# DC_DC_15V_AND_VAR.net
KiCad netlist of a schematic drawn in Altium Designer
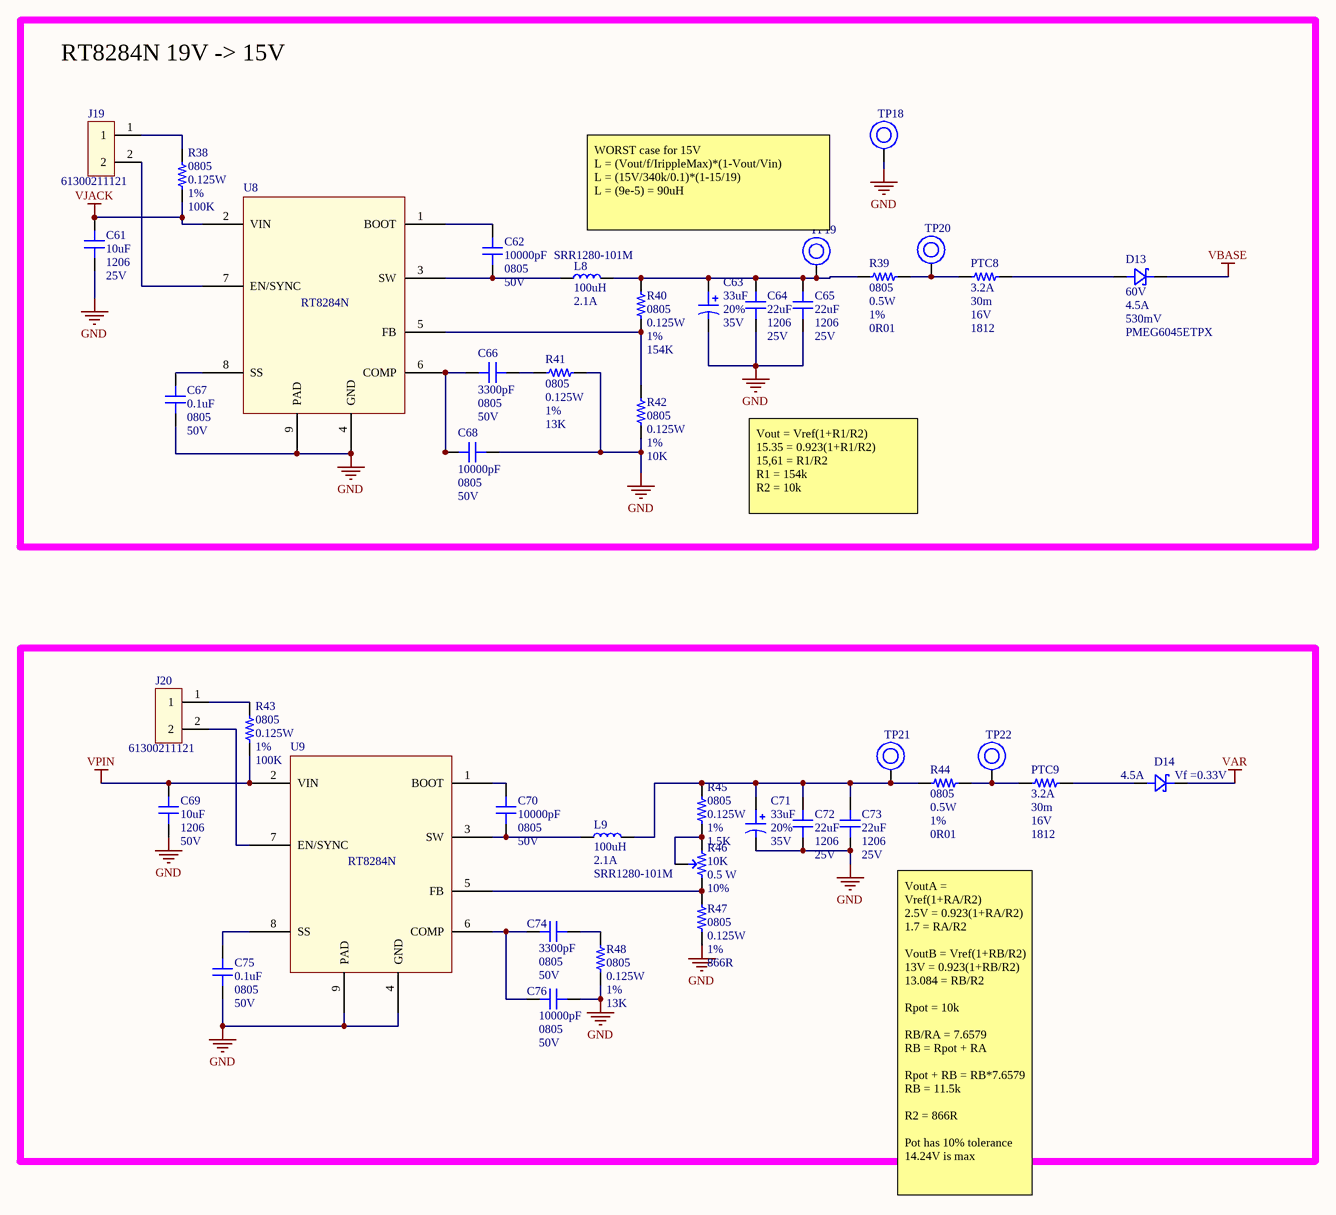
[diagram p0: DC_DC_15V_AND_VAR.SchDoc]

(export (version "E")
  (design (tool "Eeschema 10.0.6"))
  (components
    (comp (ref "C61")
      (value "10uF")
      (footprint "CAP_1206")
      (description "CAP CER 10uF 25V 1206")
      (fields
        (field (name "PART NUMBER") "CL31A106KAHNFNE‎")
        (field (name "PACKAGE") "1206")
        (field (name "VOLTAGE") "25V")
        (field (name "Comment") "CAP_‎CL31A106KAHNFNE‎")
      )
      (libsource (lib "SecureBot") (part "CAP_‎CL31A106KAHNFNE‎"))
    )
    (comp (ref "C62")
      (value "10000pF")
      (footprint "CAP_0805")
      (description "CAP CER 10000pF 50V 0805")
      (fields
        (field (name "PART NUMBER") "‎CL21B103KBANNNC")
        (field (name "PACKAGE") "0805")
        (field (name "VOLTAGE") "50V")
        (field (name "Comment") "CAP_‎‎‎‎CL21B103KBANNNC")
      )
      (libsource (lib "SecureBot") (part "CAP_‎‎‎‎CL21B103KBANNNC"))
    )
    (comp (ref "C63")
      (value "33uF")
      (footprint "CAP ALU - 6.3mm DIA")
      (description "CAP ALU 33µF 35V")
      (fields
        (field (name "PART NUMBER") "EEE-FK1V330P")
        (field (name "TOLERANCE") "20%")
        (field (name "VOLTAGE") "35V")
        (field (name "Comment") "CAP_EEE-FK1V330P")
      )
      (libsource (lib "SecureBot") (part "CAP_EEE-FK1V330P"))
    )
    (comp (ref "C64")
      (value "22uF")
      (footprint "CAP_1206")
      (description "CAP CER 22uF 25V 1206")
      (fields
        (field (name "PART NUMBER") "CL31A226KAHNNNE‎")
        (field (name "PACKAGE") "1206")
        (field (name "VOLTAGE") "25V")
        (field (name "Comment") "CAP_‎‎CL31A226KAHNNNE‎")
      )
      (libsource (lib "SecureBot") (part "CAP_‎‎CL31A226KAHNNNE‎"))
    )
    (comp (ref "C65")
      (value "22uF")
      (footprint "CAP_1206")
      (description "CAP CER 22uF 25V 1206")
      (fields
        (field (name "PART NUMBER") "CL31A226KAHNNNE‎")
        (field (name "PACKAGE") "1206")
        (field (name "VOLTAGE") "25V")
        (field (name "Comment") "CAP_‎‎CL31A226KAHNNNE‎")
      )
      (libsource (lib "SecureBot") (part "CAP_‎‎CL31A226KAHNNNE‎"))
    )
    (comp (ref "C66")
      (value "3300pF")
      (footprint "CAP_0805")
      (description "CAP CER 3300pF 50V 0805")
      (fields
        (field (name "PART NUMBER") "CL21B332KBANNNC‎")
        (field (name "PACKAGE") "0805")
        (field (name "VOLTAGE") "50V")
        (field (name "Comment") "CAP_CL21B332KBANNNC‎")
      )
      (libsource (lib "SecureBot") (part "CAP_CL21B332KBANNNC‎"))
    )
    (comp (ref "C67")
      (value "0.1uF")
      (footprint "CAP_0805")
      (description "CAP CER 0.1uF 50V 0805")
      (fields
        (field (name "PART NUMBER") "CC0805KRX7R9BB104‎")
        (field (name "PACKAGE") "0805")
        (field (name "VOLTAGE") "50V")
        (field (name "Comment") "CAP_CC0805KRX7R9BB104‎")
      )
      (libsource (lib "SecureBot") (part "CAP_CC0805KRX7R9BB104‎"))
    )
    (comp (ref "C68")
      (value "10000pF")
      (footprint "CAP_0805")
      (description "CAP CER 10000pF 50V 0805")
      (fields
        (field (name "PART NUMBER") "‎CL21B103KBANNNC")
        (field (name "PACKAGE") "0805")
        (field (name "VOLTAGE") "50V")
        (field (name "Comment") "CAP_‎‎‎‎CL21B103KBANNNC")
      )
      (libsource (lib "SecureBot") (part "CAP_‎‎‎‎CL21B103KBANNNC"))
    )
    (comp (ref "C69")
      (value "10uF")
      (footprint "CAP_1206")
      (description "CAP CER 10uF 50V 1206")
      (fields
        (field (name "PART NUMBER") "GRT31CR61H106ME01L‎")
        (field (name "PACKAGE") "1206")
        (field (name "VOLTAGE") "50V")
        (field (name "Comment") "CAP_GRT31CR61H106ME01L‎")
      )
      (libsource (lib "SecureBot") (part "CAP_GRT31CR61H106ME01L‎"))
    )
    (comp (ref "C70")
      (value "10000pF")
      (footprint "CAP_0805")
      (description "CAP CER 10000pF 50V 0805")
      (fields
        (field (name "PART NUMBER") "‎CL21B103KBANNNC")
        (field (name "PACKAGE") "0805")
        (field (name "VOLTAGE") "50V")
        (field (name "Comment") "CAP_‎‎‎‎CL21B103KBANNNC")
      )
      (libsource (lib "SecureBot") (part "CAP_‎‎‎‎CL21B103KBANNNC"))
    )
    (comp (ref "C71")
      (value "33uF")
      (footprint "CAP ALU - 6.3mm DIA")
      (description "CAP ALU 33µF 35V")
      (fields
        (field (name "PART NUMBER") "EEE-FK1V330P")
        (field (name "TOLERANCE") "20%")
        (field (name "VOLTAGE") "35V")
        (field (name "Comment") "CAP_EEE-FK1V330P")
      )
      (libsource (lib "SecureBot") (part "CAP_EEE-FK1V330P"))
    )
    (comp (ref "C72")
      (value "22uF")
      (footprint "CAP_1206")
      (description "CAP CER 22uF 25V 1206")
      (fields
        (field (name "PART NUMBER") "CL31A226KAHNNNE‎")
        (field (name "PACKAGE") "1206")
        (field (name "VOLTAGE") "25V")
        (field (name "Comment") "CAP_‎‎CL31A226KAHNNNE‎")
      )
      (libsource (lib "SecureBot") (part "CAP_‎‎CL31A226KAHNNNE‎"))
    )
    (comp (ref "C73")
      (value "22uF")
      (footprint "CAP_1206")
      (description "CAP CER 22uF 25V 1206")
      (fields
        (field (name "PART NUMBER") "CL31A226KAHNNNE‎")
        (field (name "PACKAGE") "1206")
        (field (name "VOLTAGE") "25V")
        (field (name "Comment") "CAP_‎‎CL31A226KAHNNNE‎")
      )
      (libsource (lib "SecureBot") (part "CAP_‎‎CL31A226KAHNNNE‎"))
    )
    (comp (ref "C74")
      (value "3300pF")
      (footprint "CAP_0805")
      (description "CAP CER 3300pF 50V 0805")
      (fields
        (field (name "PART NUMBER") "CL21B332KBANNNC‎")
        (field (name "PACKAGE") "0805")
        (field (name "VOLTAGE") "50V")
        (field (name "Comment") "CAP_CL21B332KBANNNC‎")
      )
      (libsource (lib "SecureBot") (part "CAP_CL21B332KBANNNC‎"))
    )
    (comp (ref "C75")
      (value "0.1uF")
      (footprint "CAP_0805")
      (description "CAP CER 0.1uF 50V 0805")
      (fields
        (field (name "PART NUMBER") "CC0805KRX7R9BB104‎")
        (field (name "PACKAGE") "0805")
        (field (name "VOLTAGE") "50V")
        (field (name "Comment") "CAP_CC0805KRX7R9BB104‎")
      )
      (libsource (lib "SecureBot") (part "CAP_CC0805KRX7R9BB104‎"))
    )
    (comp (ref "C76")
      (value "10000pF")
      (footprint "CAP_0805")
      (description "CAP CER 10000pF 50V 0805")
      (fields
        (field (name "PART NUMBER") "‎CL21B103KBANNNC")
        (field (name "PACKAGE") "0805")
        (field (name "VOLTAGE") "50V")
        (field (name "Comment") "CAP_‎‎‎‎CL21B103KBANNNC")
      )
      (libsource (lib "SecureBot") (part "CAP_‎‎‎‎CL21B103KBANNNC"))
    )
    (comp (ref "D13")
      (value "DIODE_SCH_PMEG6045ETPX")
      (footprint "DO-214AC_SOD128")
      (description "Diode Schottky 60V 4.5A Surface Mount CFP5")
      (fields
        (field (name "VOLTAGE") "60V")
        (field (name "CURRENT") "4.5A")
        (field (name "VF") "530mV")
        (field (name "PART NUMBER") "PMEG6045ETPX")
      )
      (libsource (lib "SecureBot") (part "DIODE_SCH_PMEG6045ETPX"))
    )
    (comp (ref "D14")
      (value "SCHOTTKEY")
      (footprint "DO-214AC_SOD128")
      (fields
        (field (name "CURRENT") "4.5A")
        (field (name "VF") "Vf =0.33V")
        (field (name "PART NUMBER") "PMEG6045ETPX")
      )
      (libsource (lib "SecureBot") (part "SCHOTTKEY"))
    )
    (comp (ref "J19")
      (value "Header 2 pin SM")
      (footprint "HDR1X2")
      (fields (field (name "PART NUMBER") "61300211121"))
      (libsource (lib "SecureBot") (part "Header 2 pin SM"))
    )
    (comp (ref "J20")
      (value "Header 2 pin SM")
      (footprint "HDR1X2")
      (fields (field (name "PART NUMBER") "61300211121"))
      (libsource (lib "SecureBot") (part "Header 2 pin SM"))
    )
    (comp (ref "L8")
      (value "100uH")
      (footprint "BOURNS 12.5x12.5mm")
      (description "IND 100µH Shielded Wirewound Inductor 2.1A")
      (fields
        (field (name "TOLERANCE") "20%")
        (field (name "CURRENT") "2.1A")
        (field (name "PART NUMBER") "SRR1280-101M")
        (field (name "Comment") "IND_SRR1280-101M")
      )
      (libsource (lib "SecureBot") (part "IND_SRR1280-101M"))
    )
    (comp (ref "L9")
      (value "100uH")
      (footprint "BOURNS 12.5x12.5mm")
      (description "IND 100µH Shielded Wirewound Inductor 2.1A")
      (fields
        (field (name "TOLERANCE") "20%")
        (field (name "CURRENT") "2.1A")
        (field (name "PART NUMBER") "SRR1280-101M")
        (field (name "Comment") "IND_SRR1280-101M")
      )
      (libsource (lib "SecureBot") (part "IND_SRR1280-101M"))
    )
    (comp (ref "PTC8")
      (value "PTC_0ZCG0160BF2C")
      (footprint "PTC - 1812")
      (description "PTC_Polymeric PTC Resettable Fuse 16V 1.6A Ih")
      (fields
        (field (name "PART NUMBER") "0ZCG0160BF2C")
        (field (name "TRIP VALUE") "3.2A")
        (field (name "RES") "30m")
        (field (name "VOLTAGE") "16V")
        (field (name "PACKAGE") "1812")
      )
      (libsource (lib "SecureBot") (part "PTC_0ZCG0160BF2C"))
    )
    (comp (ref "PTC9")
      (value "PTC_0ZCG0160BF2C")
      (footprint "PTC - 1812")
      (description "PTC_Polymeric PTC Resettable Fuse 16V 1.6A Ih")
      (fields
        (field (name "PART NUMBER") "0ZCG0160BF2C")
        (field (name "TRIP VALUE") "3.2A")
        (field (name "RES") "30m")
        (field (name "VOLTAGE") "16V")
        (field (name "PACKAGE") "1812")
      )
      (libsource (lib "SecureBot") (part "PTC_0ZCG0160BF2C"))
    )
    (comp (ref "R38")
      (value "100K")
      (footprint "RES_0805")
      (description "RES 100K 1% 1/8W 0805")
      (fields
        (field (name "PART NUMBER") "‎RMCF0805FT100K‎")
        (field (name "PACKAGE") "0805")
        (field (name "POWER") "0.125W")
        (field (name "TOLERANCE") "1%")
        (field (name "Comment") "RES_‎RMCF0805FT100K‎")
      )
      (libsource (lib "SecureBot") (part "RES_‎RMCF0805FT100K‎"))
    )
    (comp (ref "R39")
      (value "0R01")
      (footprint "RES_0805")
      (description "RES 0.01R 1% 1/2W 0805")
      (fields
        (field (name "PART NUMBER") "KRL1220E-M-R010-F-T5")
        (field (name "PACKAGE") "0805")
        (field (name "POWER") "0.5W")
        (field (name "TOLERANCE") "1%")
        (field (name "Comment") "RES_‎‎‎‎‎ KRL1220E-M-R010-F-T5")
      )
      (libsource (lib "SecureBot") (part "RES_‎‎‎‎‎ KRL1220E-M-R010-F-T5"))
    )
    (comp (ref "R40")
      (value "154K")
      (footprint "RES_0805")
      (description "RES 154K 1% 1/8W 0805")
      (fields
        (field (name "PART NUMBER") "‎RC0805FR-07154KL")
        (field (name "PACKAGE") "0805")
        (field (name "POWER") "0.125W")
        (field (name "TOLERANCE") "1%")
        (field (name "Comment") "RES_‎‎RC0805FR-07154KL")
      )
      (libsource (lib "SecureBot") (part "RES_‎‎RC0805FR-07154KL"))
    )
    (comp (ref "R41")
      (value "13K")
      (footprint "RES_0805")
      (description "RES 13K 1% 1/8W 0805")
      (fields
        (field (name "PART NUMBER") "RC0805FR-0713KL")
        (field (name "PACKAGE") "0805")
        (field (name "POWER") "0.125W")
        (field (name "TOLERANCE") "1%")
        (field (name "Comment") "RES_‎ RC0805FR-0713KL")
      )
      (libsource (lib "SecureBot") (part "RES_‎ RC0805FR-0713KL"))
    )
    (comp (ref "R42")
      (value "10K")
      (footprint "RES_0805")
      (description "RES 10K 1% 1/8W 0805")
      (fields
        (field (name "PART NUMBER") "RMCF0805FT10K0")
        (field (name "PACKAGE") "0805")
        (field (name "POWER") "0.125W")
        (field (name "TOLERANCE") "1%")
        (field (name "Comment") "RES_‎RMCF0805FT10K0")
      )
      (libsource (lib "SecureBot") (part "RES_‎RMCF0805FT10K0"))
    )
    (comp (ref "R43")
      (value "100K")
      (footprint "RES_0805")
      (description "RES 100K 1% 1/8W 0805")
      (fields
        (field (name "PART NUMBER") "‎RMCF0805FT100K‎")
        (field (name "PACKAGE") "0805")
        (field (name "POWER") "0.125W")
        (field (name "TOLERANCE") "1%")
        (field (name "Comment") "RES_‎RMCF0805FT100K‎")
      )
      (libsource (lib "SecureBot") (part "RES_‎RMCF0805FT100K‎"))
    )
    (comp (ref "R44")
      (value "0R01")
      (footprint "RES_0805")
      (description "RES 0.01R 1% 1/2W 0805")
      (fields
        (field (name "PART NUMBER") "KRL1220E-M-R010-F-T5")
        (field (name "PACKAGE") "0805")
        (field (name "POWER") "0.5W")
        (field (name "TOLERANCE") "1%")
        (field (name "Comment") "RES_‎‎‎‎‎ KRL1220E-M-R010-F-T5")
      )
      (libsource (lib "SecureBot") (part "RES_‎‎‎‎‎ KRL1220E-M-R010-F-T5"))
    )
    (comp (ref "R45")
      (value "1.5K")
      (footprint "RES_0805")
      (description "RES 1.5K 1% 1/8W 0805")
      (fields
        (field (name "PART NUMBER") "CRCW08051K50FKEAC")
        (field (name "PACKAGE") "0805")
        (field (name "POWER") "0.125W")
        (field (name "TOLERANCE") "1%")
        (field (name "Comment") "RES_‎‎‎‎CRCW08051K50FKEAC")
      )
      (libsource (lib "SecureBot") (part "RES_‎‎‎‎CRCW08051K50FKEAC"))
    )
    (comp (ref "R46")
      (value "10K")
      (footprint "3361P")
      (description "POT TRIMMER 10K OHM 0.5W GW TOP ADJ")
      (fields
        (field (name "PART NUMBER") "3361P-1-103GLF")
        (field (name "WATT") "0.5 W")
        (field (name "TOLERANCE") "10%")
        (field (name "Comment") "POT_3361P-1-103GLF")
      )
      (libsource (lib "SecureBot") (part "POT_3361P-1-103GLF"))
    )
    (comp (ref "R47")
      (value "866R")
      (footprint "RES_0805")
      (description "RES 866R 1% 1/8W 0805")
      (fields
        (field (name "PART NUMBER") "RC0805FR-07866RL")
        (field (name "PACKAGE") "0805")
        (field (name "POWER") "0.125W")
        (field (name "TOLERANCE") "1%")
        (field (name "Comment") "RES_‎‎‎RC0805FR-07866RL")
      )
      (libsource (lib "SecureBot") (part "RES_‎‎‎RC0805FR-07866RL"))
    )
    (comp (ref "R48")
      (value "13K")
      (footprint "RES_0805")
      (description "RES 13K 1% 1/8W 0805")
      (fields
        (field (name "PART NUMBER") "RC0805FR-0713KL")
        (field (name "PACKAGE") "0805")
        (field (name "POWER") "0.125W")
        (field (name "TOLERANCE") "1%")
        (field (name "Comment") "RES_‎ RC0805FR-0713KL")
      )
      (libsource (lib "SecureBot") (part "RES_‎ RC0805FR-0713KL"))
    )
    (comp (ref "TP18")
      (value "TestPoint 3x3mm")
      (footprint "TestPoint 3X3mm")
      (libsource (lib "SecureBot") (part "TestPoint 3x3mm"))
    )
    (comp (ref "TP19")
      (value "TestPoint 3x3mm")
      (footprint "TestPoint 3X3mm")
      (libsource (lib "SecureBot") (part "TestPoint 3x3mm"))
    )
    (comp (ref "TP20")
      (value "TestPoint 3x3mm")
      (footprint "TestPoint 3X3mm")
      (libsource (lib "SecureBot") (part "TestPoint 3x3mm"))
    )
    (comp (ref "TP21")
      (value "TestPoint 3x3mm")
      (footprint "TestPoint 3X3mm")
      (libsource (lib "SecureBot") (part "TestPoint 3x3mm"))
    )
    (comp (ref "TP22")
      (value "TestPoint 3x3mm")
      (footprint "TestPoint 3X3mm")
      (libsource (lib "SecureBot") (part "TestPoint 3x3mm"))
    )
    (comp (ref "U8")
      (value "REG_SW_RT8284N")
      (footprint "SOP8")
      (description "REG 2A, 23V, 340kHz Synchronous Step-Down Converter")
      (fields (field (name "PART NUMBER") "RT8284N"))
      (libsource (lib "SecureBot") (part "REG_SW_RT8284N"))
    )
    (comp (ref "U9")
      (value "REG_SW_RT8284N")
      (footprint "SOP8")
      (description "REG 2A, 23V, 340kHz Synchronous Step-Down Converter")
      (fields (field (name "PART NUMBER") "RT8284N"))
      (libsource (lib "SecureBot") (part "REG_SW_RT8284N"))
    )
  )
  (nets
    (net (code "1") (name "GND") (class "Default")
      (node (ref "C61") (pin "2") (pinfunction "2_2") (pintype "passive"))
      (node (ref "C63") (pin "2") (pinfunction "2_2") (pintype "passive"))
      (node (ref "C64") (pin "2") (pinfunction "2_2") (pintype "passive"))
      (node (ref "C65") (pin "2") (pinfunction "2_2") (pintype "passive"))
      (node (ref "C67") (pin "2") (pinfunction "2_2") (pintype "passive"))
      (node (ref "C68") (pin "2") (pinfunction "2_2") (pintype "passive"))
      (node (ref "C69") (pin "2") (pinfunction "2_2") (pintype "passive"))
      (node (ref "C71") (pin "2") (pinfunction "2_2") (pintype "passive"))
      (node (ref "C72") (pin "2") (pinfunction "2_2") (pintype "passive"))
      (node (ref "C73") (pin "2") (pinfunction "2_2") (pintype "passive"))
      (node (ref "C75") (pin "2") (pinfunction "2_2") (pintype "passive"))
      (node (ref "C76") (pin "2") (pinfunction "2_2") (pintype "passive"))
      (node (ref "R41") (pin "1") (pinfunction "1_1") (pintype "passive"))
      (node (ref "R42") (pin "2") (pinfunction "2_2") (pintype "passive"))
      (node (ref "R47") (pin "2") (pinfunction "2_2") (pintype "passive"))
      (node (ref "R48") (pin "2") (pinfunction "2_2") (pintype "passive"))
      (node (ref "TP18") (pin "1") (pinfunction "1_1") (pintype "passive"))
      (node (ref "U8") (pin "4") (pinfunction "GND_4") (pintype "passive"))
      (node (ref "U8") (pin "9") (pinfunction "PAD_9") (pintype "passive"))
      (node (ref "U9") (pin "4") (pinfunction "GND_4") (pintype "passive"))
      (node (ref "U9") (pin "9") (pinfunction "PAD_9") (pintype "passive"))
    )
    (net (code "2") (name "Net-(C63-Pad1)") (class "Default")
      (node (ref "C63") (pin "1") (pinfunction "1_1") (pintype "passive"))
      (node (ref "C64") (pin "1") (pinfunction "1_1") (pintype "passive"))
      (node (ref "C65") (pin "1") (pinfunction "1_1") (pintype "passive"))
      (node (ref "L8") (pin "2") (pinfunction "2_2") (pintype "passive"))
      (node (ref "R39") (pin "1") (pinfunction "1_1") (pintype "passive"))
      (node (ref "R40") (pin "1") (pinfunction "1_1") (pintype "passive"))
      (node (ref "TP19") (pin "1") (pinfunction "1_1") (pintype "passive"))
    )
    (net (code "3") (name "Net-(C66-Pad2)") (class "Default")
      (node (ref "C66") (pin "2") (pinfunction "2_2") (pintype "passive"))
      (node (ref "R41") (pin "2") (pinfunction "2_2") (pintype "passive"))
    )
    (net (code "4") (name "Net-(C71-Pad1)") (class "Default")
      (node (ref "C71") (pin "1") (pinfunction "1_1") (pintype "passive"))
      (node (ref "C72") (pin "1") (pinfunction "1_1") (pintype "passive"))
      (node (ref "C73") (pin "1") (pinfunction "1_1") (pintype "passive"))
      (node (ref "L9") (pin "2") (pinfunction "2_2") (pintype "passive"))
      (node (ref "R44") (pin "1") (pinfunction "1_1") (pintype "passive"))
      (node (ref "R45") (pin "1") (pinfunction "1_1") (pintype "passive"))
      (node (ref "TP21") (pin "1") (pinfunction "1_1") (pintype "passive"))
    )
    (net (code "5") (name "Net-(C74-Pad2)") (class "Default")
      (node (ref "C74") (pin "2") (pinfunction "2_2") (pintype "passive"))
      (node (ref "R48") (pin "1") (pinfunction "1_1") (pintype "passive"))
    )
    (net (code "6") (name "Net-(D13-Pad1)") (class "Default")
      (node (ref "D13") (pin "1") (pinfunction "1_1") (pintype "passive"))
      (node (ref "PTC8") (pin "2") (pinfunction "2_2") (pintype "passive"))
    )
    (net (code "7") (name "Net-(D14-Pad1)") (class "Default")
      (node (ref "D14") (pin "1") (pinfunction "1_1") (pintype "passive"))
      (node (ref "PTC9") (pin "2") (pinfunction "2_2") (pintype "passive"))
    )
    (net (code "8") (name "Net-(J19-Pad1)") (class "Default")
      (node (ref "J19") (pin "1") (pinfunction "1_1") (pintype "passive"))
      (node (ref "R38") (pin "1") (pinfunction "1_1") (pintype "passive"))
    )
    (net (code "9") (name "Net-(J20-Pad1)") (class "Default")
      (node (ref "J20") (pin "1") (pinfunction "1_1") (pintype "passive"))
      (node (ref "R43") (pin "1") (pinfunction "1_1") (pintype "passive"))
    )
    (net (code "10") (name "Net-(PTC8-Pad1)") (class "Default")
      (node (ref "PTC8") (pin "1") (pinfunction "1_1") (pintype "passive"))
      (node (ref "R39") (pin "2") (pinfunction "2_2") (pintype "passive"))
      (node (ref "TP20") (pin "1") (pinfunction "1_1") (pintype "passive"))
    )
    (net (code "11") (name "Net-(PTC9-Pad1)") (class "Default")
      (node (ref "PTC9") (pin "1") (pinfunction "1_1") (pintype "passive"))
      (node (ref "R44") (pin "2") (pinfunction "2_2") (pintype "passive"))
      (node (ref "TP22") (pin "1") (pinfunction "1_1") (pintype "passive"))
    )
    (net (code "12") (name "Net-(R45-Pad2)") (class "Default")
      (node (ref "R45") (pin "2") (pinfunction "2_2") (pintype "passive"))
      (node (ref "R46") (pin "1") (pinfunction "1_1") (pintype "passive"))
      (node (ref "R46") (pin "3") (pinfunction "3_3") (pintype "passive"))
    )
    (net (code "13") (name "Net-(U8-BOOT)") (class "Default")
      (node (ref "C62") (pin "1") (pinfunction "1_1") (pintype "passive"))
      (node (ref "U8") (pin "1") (pinfunction "BOOT_1") (pintype "passive"))
    )
    (net (code "14") (name "Net-(U8-COMP)") (class "Default")
      (node (ref "C66") (pin "1") (pinfunction "1_1") (pintype "passive"))
      (node (ref "C68") (pin "1") (pinfunction "1_1") (pintype "passive"))
      (node (ref "U8") (pin "6") (pinfunction "COMP_6") (pintype "passive"))
    )
    (net (code "15") (name "Net-(U8-EN{slash}SYNC)") (class "Default")
      (node (ref "J19") (pin "2") (pinfunction "2_2") (pintype "passive"))
      (node (ref "U8") (pin "7") (pinfunction "EN/SYNC_7") (pintype "passive"))
    )
    (net (code "16") (name "Net-(U8-FB)") (class "Default")
      (node (ref "R40") (pin "2") (pinfunction "2_2") (pintype "passive"))
      (node (ref "R42") (pin "1") (pinfunction "1_1") (pintype "passive"))
      (node (ref "U8") (pin "5") (pinfunction "FB_5") (pintype "passive"))
    )
    (net (code "17") (name "Net-(U8-SS)") (class "Default")
      (node (ref "C67") (pin "1") (pinfunction "1_1") (pintype "passive"))
      (node (ref "U8") (pin "8") (pinfunction "SS_8") (pintype "passive"))
    )
    (net (code "18") (name "Net-(U8-SW)") (class "Default")
      (node (ref "C62") (pin "2") (pinfunction "2_2") (pintype "passive"))
      (node (ref "L8") (pin "1") (pinfunction "1_1") (pintype "passive"))
      (node (ref "U8") (pin "3") (pinfunction "SW_3") (pintype "passive"))
    )
    (net (code "19") (name "Net-(U9-BOOT)") (class "Default")
      (node (ref "C70") (pin "1") (pinfunction "1_1") (pintype "passive"))
      (node (ref "U9") (pin "1") (pinfunction "BOOT_1") (pintype "passive"))
    )
    (net (code "20") (name "Net-(U9-COMP)") (class "Default")
      (node (ref "C74") (pin "1") (pinfunction "1_1") (pintype "passive"))
      (node (ref "C76") (pin "1") (pinfunction "1_1") (pintype "passive"))
      (node (ref "U9") (pin "6") (pinfunction "COMP_6") (pintype "passive"))
    )
    (net (code "21") (name "Net-(U9-EN{slash}SYNC)") (class "Default")
      (node (ref "J20") (pin "2") (pinfunction "2_2") (pintype "passive"))
      (node (ref "U9") (pin "7") (pinfunction "EN/SYNC_7") (pintype "passive"))
    )
    (net (code "22") (name "Net-(U9-FB)") (class "Default")
      (node (ref "R46") (pin "2") (pinfunction "2_2") (pintype "passive"))
      (node (ref "R47") (pin "1") (pinfunction "1_1") (pintype "passive"))
      (node (ref "U9") (pin "5") (pinfunction "FB_5") (pintype "passive"))
    )
    (net (code "23") (name "Net-(U9-SS)") (class "Default")
      (node (ref "C75") (pin "1") (pinfunction "1_1") (pintype "passive"))
      (node (ref "U9") (pin "8") (pinfunction "SS_8") (pintype "passive"))
    )
    (net (code "24") (name "Net-(U9-SW)") (class "Default")
      (node (ref "C70") (pin "2") (pinfunction "2_2") (pintype "passive"))
      (node (ref "L9") (pin "1") (pinfunction "1_1") (pintype "passive"))
      (node (ref "U9") (pin "3") (pinfunction "SW_3") (pintype "passive"))
    )
    (net (code "25") (name "VAR") (class "Default")
      (node (ref "D14") (pin "2") (pinfunction "2_2") (pintype "passive"))
    )
    (net (code "26") (name "VBASE") (class "Default")
      (node (ref "D13") (pin "2") (pinfunction "2_2") (pintype "passive"))
    )
    (net (code "27") (name "VJACK") (class "Default")
      (node (ref "C61") (pin "1") (pinfunction "1_1") (pintype "passive"))
      (node (ref "R38") (pin "2") (pinfunction "2_2") (pintype "passive"))
      (node (ref "U8") (pin "2") (pinfunction "VIN_2") (pintype "passive"))
    )
    (net (code "28") (name "VPIN") (class "Default")
      (node (ref "C69") (pin "1") (pinfunction "1_1") (pintype "passive"))
      (node (ref "R43") (pin "2") (pinfunction "2_2") (pintype "passive"))
      (node (ref "U9") (pin "2") (pinfunction "VIN_2") (pintype "passive"))
    )
  )
)
